# LED_Driver.net
KiCad netlist of a schematic drawn in Altium Designer
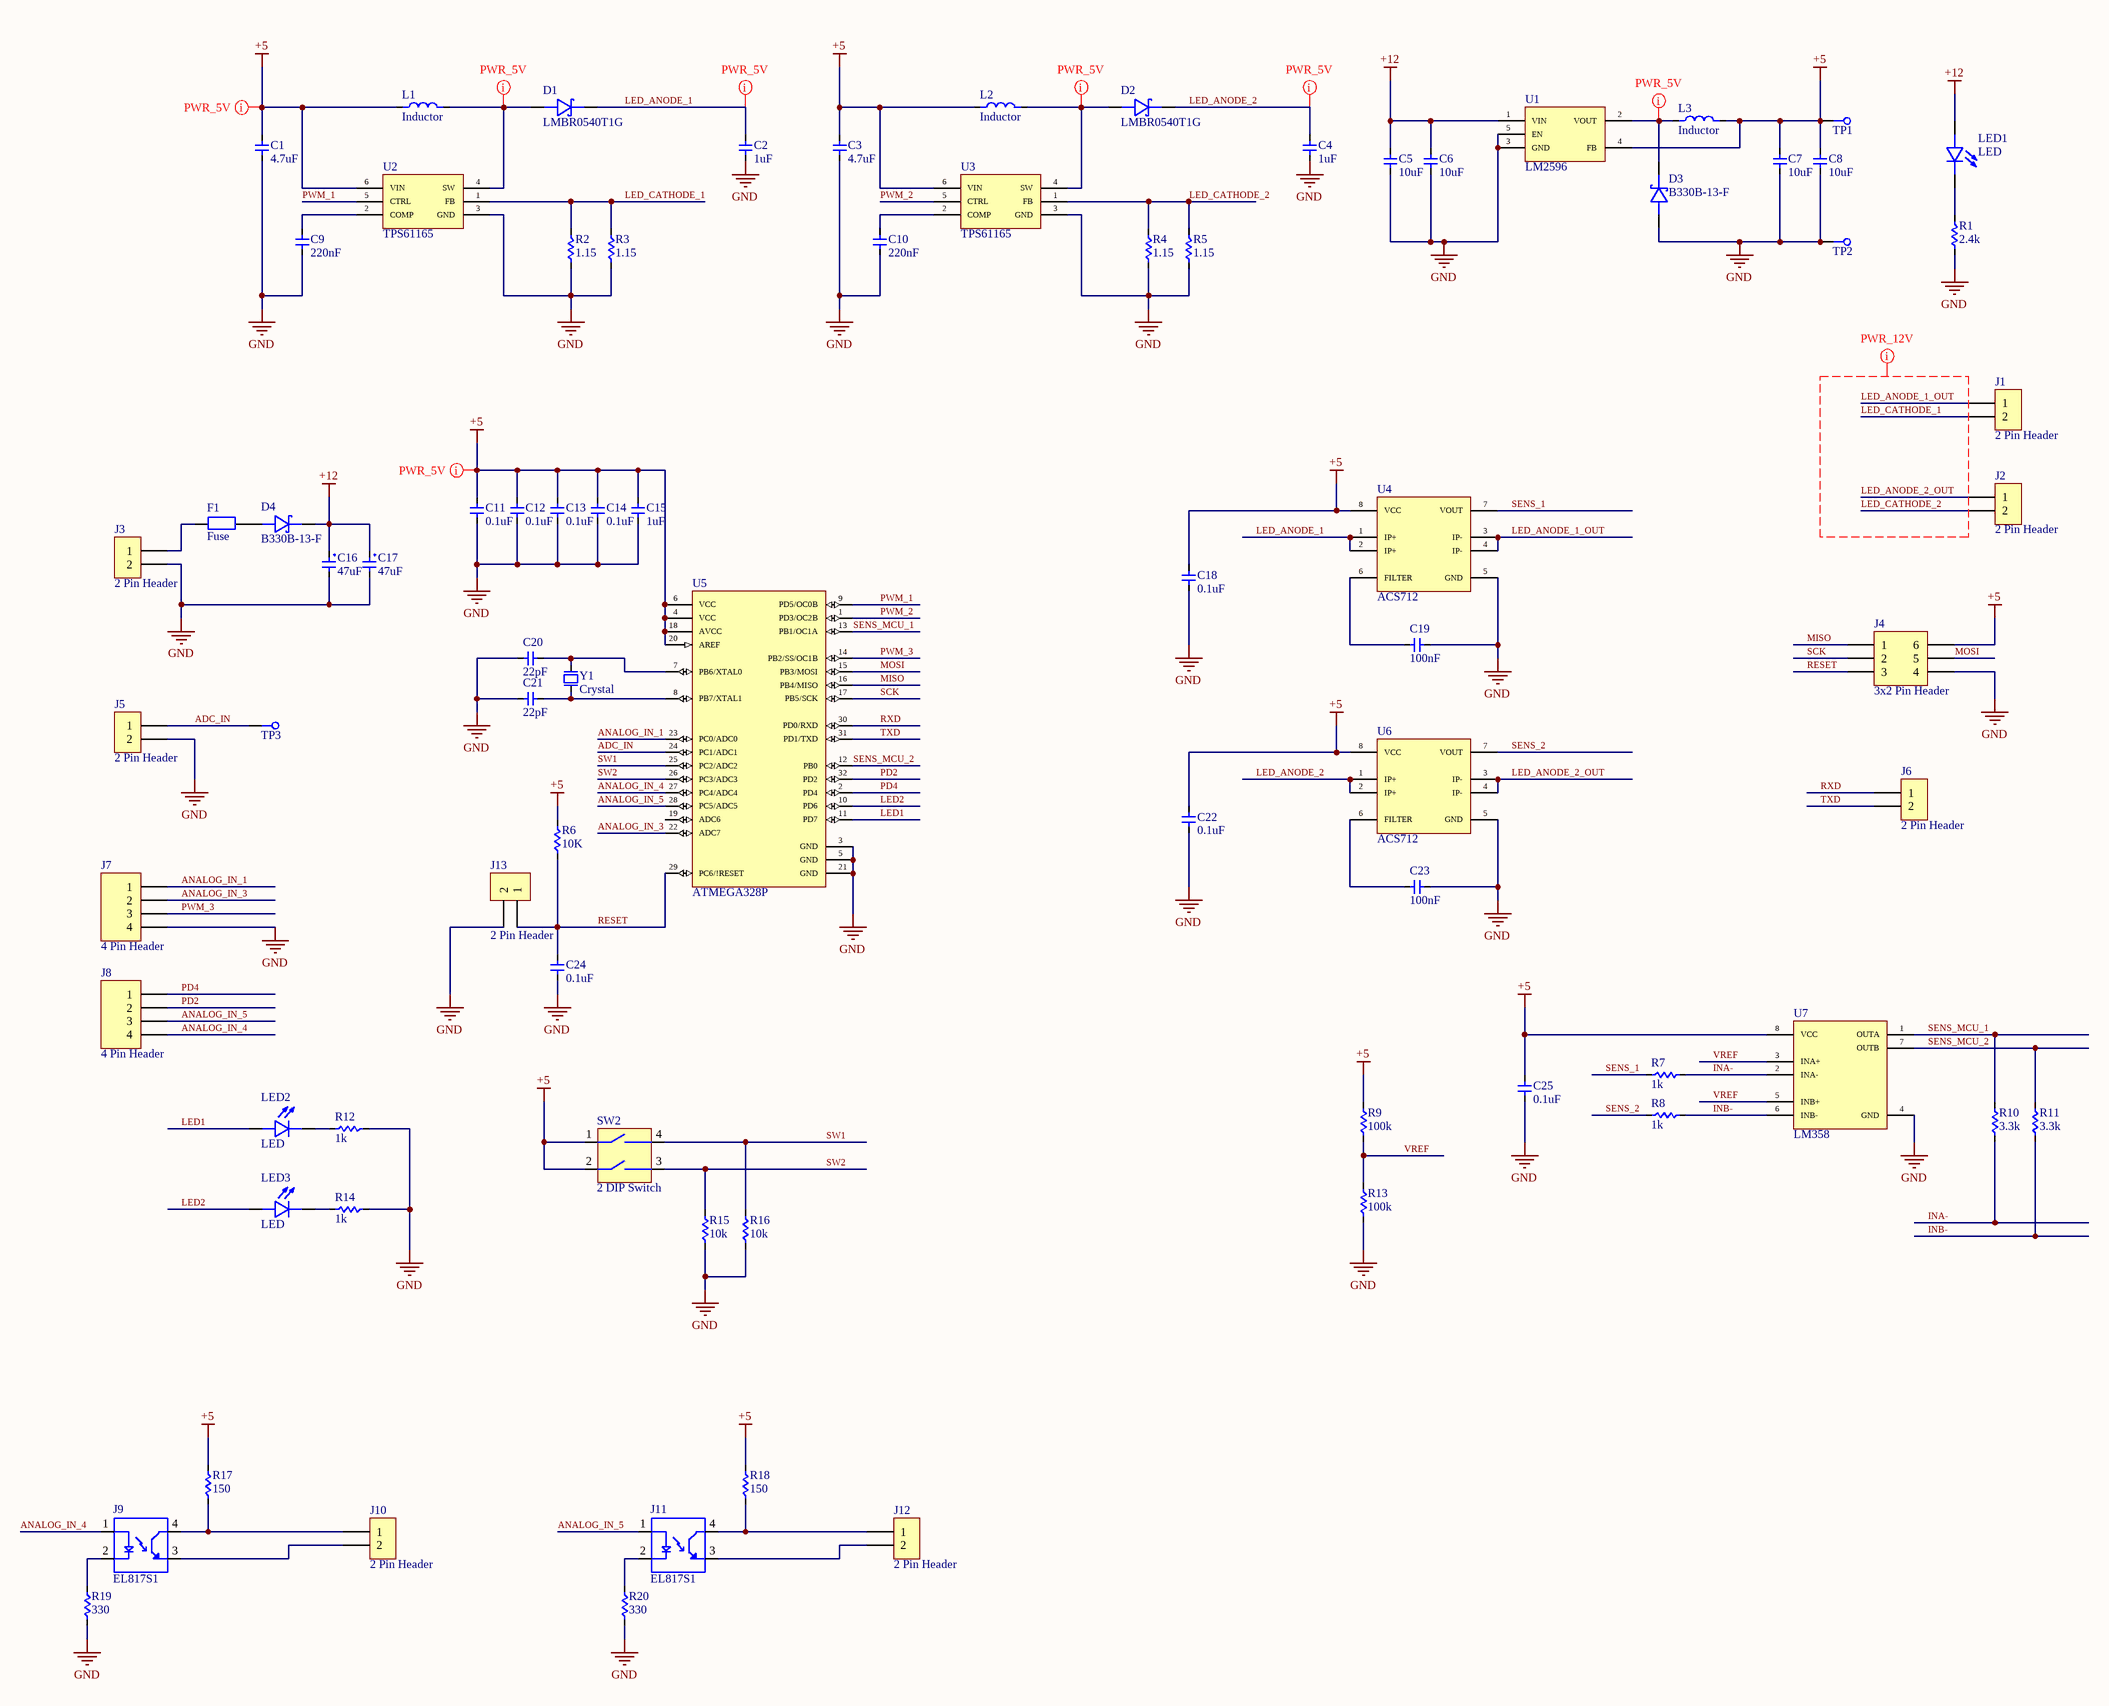
[diagram p0: LED Driver.SchDoc]

(export (version "E")
  (design (tool "Eeschema 10.0.6"))
  (components
    (comp (ref "C1") (value "4.7uF") (footprint "RES603") (libsource (lib "Schlib") (part "Capacitor")))
    (comp (ref "C2") (value "1uF") (footprint "RES603") (libsource (lib "Schlib") (part "Capacitor")))
    (comp (ref "C3") (value "4.7uF") (footprint "RES603") (libsource (lib "Schlib") (part "Capacitor")))
    (comp (ref "C4") (value "1uF") (footprint "RES603") (libsource (lib "Schlib") (part "Capacitor")))
    (comp (ref "C5") (value "10uF") (footprint "RES603") (libsource (lib "Schlib") (part "Capacitor")))
    (comp (ref "C6") (value "10uF") (footprint "RES603") (libsource (lib "Schlib") (part "Capacitor")))
    (comp (ref "C7") (value "10uF") (footprint "RES603") (libsource (lib "Schlib") (part "Capacitor")))
    (comp (ref "C8") (value "10uF") (footprint "RES603") (libsource (lib "Schlib") (part "Capacitor")))
    (comp (ref "C9") (value "220nF") (footprint "RES603") (libsource (lib "Schlib") (part "Capacitor")))
    (comp (ref "C10") (value "220nF") (footprint "RES603") (libsource (lib "Schlib") (part "Capacitor")))
    (comp (ref "C11") (value "0.1uF") (footprint "RES603") (libsource (lib "Schlib") (part "Capacitor")))
    (comp (ref "C12") (value "0.1uF") (footprint "RES603") (libsource (lib "Schlib") (part "Capacitor")))
    (comp (ref "C13") (value "0.1uF") (footprint "RES603") (libsource (lib "Schlib") (part "Capacitor")))
    (comp (ref "C14") (value "0.1uF") (footprint "RES603") (libsource (lib "Schlib") (part "Capacitor")))
    (comp (ref "C15") (value "1uF") (footprint "RES603") (libsource (lib "Schlib") (part "Capacitor")))
    (comp (ref "C16")
      (value "47uF")
      (footprint "VEJ470M1HTR-0607")
      (libsource (lib "Schlib") (part "Cap Pol"))
    )
    (comp (ref "C17")
      (value "47uF")
      (footprint "VEJ470M1HTR-0607")
      (libsource (lib "Schlib") (part "Cap Pol"))
    )
    (comp (ref "C18") (value "0.1uF") (footprint "RES603") (libsource (lib "Schlib") (part "Capacitor")))
    (comp (ref "C19") (value "100nF") (footprint "RES603") (libsource (lib "Schlib") (part "Capacitor")))
    (comp (ref "C20") (value "22pF") (footprint "RES603") (libsource (lib "Schlib") (part "Capacitor")))
    (comp (ref "C21") (value "22pF") (footprint "RES603") (libsource (lib "Schlib") (part "Capacitor")))
    (comp (ref "C22") (value "0.1uF") (footprint "RES603") (libsource (lib "Schlib") (part "Capacitor")))
    (comp (ref "C23") (value "100nF") (footprint "RES603") (libsource (lib "Schlib") (part "Capacitor")))
    (comp (ref "C24") (value "0.1uF") (footprint "RES603") (libsource (lib "Schlib") (part "Capacitor")))
    (comp (ref "C25") (value "0.1uF") (footprint "RES603") (libsource (lib "Schlib") (part "Capacitor")))
    (comp (ref "D1")
      (value "LMBR0540T1G")
      (footprint "LMBR0540T1G")
      (libsource (lib "Schlib") (part "Schottky Diode"))
    )
    (comp (ref "D2")
      (value "LMBR0540T1G")
      (footprint "LMBR0540T1G")
      (libsource (lib "Schlib") (part "Schottky Diode"))
    )
    (comp (ref "D3")
      (value "B330B-13-F")
      (footprint "B330B-13-F")
      (libsource (lib "Schlib") (part "Schottky Diode"))
    )
    (comp (ref "D4")
      (value "B330B-13-F")
      (footprint "B330B-13-F")
      (libsource (lib "Schlib") (part "Schottky Diode"))
    )
    (comp (ref "F1") (value "Fuse") (footprint "39215000000") (libsource (lib "Schlib") (part "Fuse")))
    (comp (ref "J1")
      (value "2 Pin Header")
      (footprint "2POS 2.54mm Pin Header")
      (libsource (lib "Schlib") (part "2 Pin Header"))
    )
    (comp (ref "J2")
      (value "2 Pin Header")
      (footprint "2POS 2.54mm Pin Header")
      (libsource (lib "Schlib") (part "2 Pin Header"))
    )
    (comp (ref "J3")
      (value "2 Pin Header")
      (footprint "2POS 5.08mm Screw Connector")
      (libsource (lib "") (part "2 Pin Header_1"))
    )
    (comp (ref "J4")
      (value "3x2 Pin Header")
      (footprint "2x3POS 2.54mm Pin Header")
      (libsource (lib "Schlib") (part "3x2 Pin Header"))
    )
    (comp (ref "J5")
      (value "2 Pin Header")
      (footprint "2POS 2.54mm Pin Header")
      (libsource (lib "") (part "2 Pin Header_1"))
    )
    (comp (ref "J6")
      (value "2 Pin Header")
      (footprint "2POS 2.54mm Pin Header")
      (libsource (lib "Schlib") (part "2 Pin Header"))
    )
    (comp (ref "J7")
      (value "4 Pin Header")
      (footprint "4POS 2.54mm PIN Header")
      (libsource (lib "Schlib") (part "4 Pin Header"))
    )
    (comp (ref "J8")
      (value "4 Pin Header")
      (footprint "4POS 2.54mm PIN Header")
      (libsource (lib "Schlib") (part "4 Pin Header"))
    )
    (comp (ref "J9") (value "EL817S1") (footprint "EL817S1") (libsource (lib "Schlib") (part "EL817S1")))
    (comp (ref "J10")
      (value "2 Pin Header")
      (footprint "2POS 2.54mm Pin Header")
      (libsource (lib "Schlib") (part "2 Pin Header"))
    )
    (comp (ref "J11") (value "EL817S1") (footprint "EL817S1") (libsource (lib "Schlib") (part "EL817S1")))
    (comp (ref "J12")
      (value "2 Pin Header")
      (footprint "2POS 2.54mm Pin Header")
      (libsource (lib "Schlib") (part "2 Pin Header"))
    )
    (comp (ref "J13")
      (value "2 Pin Header")
      (footprint "2POS 5.08mm Screw Connector")
      (libsource (lib "Schlib") (part "2 Pin Header"))
    )
    (comp (ref "L1")
      (value "Inductor")
      (footprint "CDRH104RNP-220NC")
      (libsource (lib "Schlib") (part "Inductor"))
    )
    (comp (ref "L2")
      (value "Inductor")
      (footprint "CDRH104RNP-220NC")
      (libsource (lib "Schlib") (part "Inductor"))
    )
    (comp (ref "L3")
      (value "Inductor")
      (footprint "CDRH104RNP-220NC")
      (libsource (lib "Schlib") (part "Inductor"))
    )
    (comp (ref "LED1") (value "LED") (footprint "LED603") (libsource (lib "Schlib") (part "LED")))
    (comp (ref "LED2") (value "LED") (footprint "LED603") (libsource (lib "Schlib") (part "LED")))
    (comp (ref "LED3") (value "LED") (footprint "LED603") (libsource (lib "Schlib") (part "LED")))
    (comp (ref "R1") (value "2.4k") (footprint "RES805") (libsource (lib "Schlib") (part "Resistor")))
    (comp (ref "R2") (value "1.15") (footprint "RES805") (libsource (lib "Schlib") (part "Resistor")))
    (comp (ref "R3") (value "1.15") (footprint "RES805") (libsource (lib "Schlib") (part "Resistor")))
    (comp (ref "R4") (value "1.15") (footprint "RES805") (libsource (lib "Schlib") (part "Resistor")))
    (comp (ref "R5") (value "1.15") (footprint "RES805") (libsource (lib "Schlib") (part "Resistor")))
    (comp (ref "R6") (value "10K") (footprint "RES603") (libsource (lib "Schlib") (part "Resistor")))
    (comp (ref "R7") (value "1k") (footprint "RES603") (libsource (lib "Schlib") (part "Resistor")))
    (comp (ref "R8") (value "1k") (footprint "RES603") (libsource (lib "Schlib") (part "Resistor")))
    (comp (ref "R9") (value "100k") (footprint "RES603") (libsource (lib "Schlib") (part "Resistor")))
    (comp (ref "R10") (value "3.3k") (footprint "RES603") (libsource (lib "Schlib") (part "Resistor")))
    (comp (ref "R11") (value "3.3k") (footprint "RES603") (libsource (lib "Schlib") (part "Resistor")))
    (comp (ref "R12") (value "1k") (footprint "RES805") (libsource (lib "Schlib") (part "Resistor")))
    (comp (ref "R13") (value "100k") (footprint "RES603") (libsource (lib "Schlib") (part "Resistor")))
    (comp (ref "R14") (value "1k") (footprint "RES805") (libsource (lib "Schlib") (part "Resistor")))
    (comp (ref "R15") (value "10k") (footprint "RES603") (libsource (lib "Schlib") (part "Resistor")))
    (comp (ref "R16") (value "10k") (footprint "RES603") (libsource (lib "Schlib") (part "Resistor")))
    (comp (ref "R17") (value "150") (footprint "RES805") (libsource (lib "Schlib") (part "Resistor")))
    (comp (ref "R18") (value "150") (footprint "RES805") (libsource (lib "Schlib") (part "Resistor")))
    (comp (ref "R19") (value "330") (footprint "RES805") (libsource (lib "Schlib") (part "Resistor")))
    (comp (ref "R20") (value "330") (footprint "RES805") (libsource (lib "Schlib") (part "Resistor")))
    (comp (ref "SW2")
      (value "2 DIP Switch")
      (footprint "EM-02KP")
      (libsource (lib "Schlib") (part "2 DIP Switch"))
    )
    (comp (ref "TP1")
      (value "Test Point")
      (footprint "TP SMD")
      (libsource (lib "Schlib") (part "Test Point"))
    )
    (comp (ref "TP2")
      (value "Test Point")
      (footprint "TP SMD")
      (libsource (lib "Schlib") (part "Test Point"))
    )
    (comp (ref "TP3")
      (value "Test Point")
      (footprint "TP SMD")
      (libsource (lib "Schlib") (part "Test Point"))
    )
    (comp (ref "U1") (value "LM2596") (footprint "LM2596-TO263") (libsource (lib "Schlib") (part "LM2596")))
    (comp (ref "U2") (value "TPS61165") (footprint "TPS611DRVR") (libsource (lib "Schlib") (part "TPS61165")))
    (comp (ref "U3") (value "TPS61165") (footprint "TPS611DRVR") (libsource (lib "Schlib") (part "TPS61165")))
    (comp (ref "U4")
      (value "ACS712")
      (footprint "SOIC127P600X175-8N")
      (libsource (lib "Schlib") (part "ACS712"))
    )
    (comp (ref "U5")
      (value "ATMEGA328P")
      (footprint "ATMEGA328P-AU")
      (libsource (lib "Schlib") (part "ATMEGA328P"))
    )
    (comp (ref "U6")
      (value "ACS712")
      (footprint "SOIC127P600X175-8N")
      (libsource (lib "Schlib") (part "ACS712"))
    )
    (comp (ref "U7")
      (value "LM358")
      (footprint "SOIC127P600X175-8N")
      (libsource (lib "Schlib") (part "LM358"))
    )
    (comp (ref "Y1")
      (value "Crystal")
      (footprint "X503216MSB2GI")
      (libsource (lib "Schlib") (part "Crystal"))
    )
  )
  (nets
    (net (code "1") (name "+5") (class "Default")
      (node (ref "C1") (pin "2") (pinfunction "2_2") (pintype "passive"))
      (node (ref "C11") (pin "2") (pinfunction "2_2") (pintype "passive"))
      (node (ref "C12") (pin "2") (pinfunction "2_2") (pintype "passive"))
      (node (ref "C13") (pin "2") (pinfunction "2_2") (pintype "passive"))
      (node (ref "C14") (pin "2") (pinfunction "2_2") (pintype "passive"))
      (node (ref "C15") (pin "2") (pinfunction "2_2") (pintype "passive"))
      (node (ref "C18") (pin "2") (pinfunction "2_2") (pintype "passive"))
      (node (ref "C22") (pin "2") (pinfunction "2_2") (pintype "passive"))
      (node (ref "C25") (pin "2") (pinfunction "2_2") (pintype "passive"))
      (node (ref "C3") (pin "2") (pinfunction "2_2") (pintype "passive"))
      (node (ref "C7") (pin "2") (pinfunction "2_2") (pintype "passive"))
      (node (ref "C8") (pin "2") (pinfunction "2_2") (pintype "passive"))
      (node (ref "J4") (pin "6") (pinfunction "6_6") (pintype "passive"))
      (node (ref "L1") (pin "1") (pinfunction "1_1") (pintype "passive"))
      (node (ref "L2") (pin "1") (pinfunction "1_1") (pintype "passive"))
      (node (ref "L3") (pin "2") (pinfunction "2_2") (pintype "passive"))
      (node (ref "R17") (pin "2") (pinfunction "2_2") (pintype "passive"))
      (node (ref "R18") (pin "2") (pinfunction "2_2") (pintype "passive"))
      (node (ref "R6") (pin "2") (pinfunction "2_2") (pintype "passive"))
      (node (ref "R9") (pin "2") (pinfunction "2_2") (pintype "passive"))
      (node (ref "SW2") (pin "1") (pinfunction "1_1") (pintype "passive"))
      (node (ref "SW2") (pin "2") (pinfunction "2_2") (pintype "passive"))
      (node (ref "TP1") (pin "1") (pinfunction "1_1") (pintype "passive"))
      (node (ref "U1") (pin "4") (pinfunction "FB_4") (pintype "passive"))
      (node (ref "U2") (pin "6") (pinfunction "VIN_6") (pintype "passive"))
      (node (ref "U3") (pin "6") (pinfunction "VIN_6") (pintype "passive"))
      (node (ref "U4") (pin "8") (pinfunction "VCC_8") (pintype "passive"))
      (node (ref "U5") (pin "18") (pinfunction "AVCC_18") (pintype "power_in"))
      (node (ref "U5") (pin "20") (pinfunction "AREF_20") (pintype "input"))
      (node (ref "U5") (pin "4") (pinfunction "VCC_4") (pintype "power_in"))
      (node (ref "U5") (pin "6") (pinfunction "VCC_6") (pintype "power_in"))
      (node (ref "U6") (pin "8") (pinfunction "VCC_8") (pintype "passive"))
      (node (ref "U7") (pin "8") (pinfunction "VCC_8") (pintype "passive"))
    )
    (net (code "2") (name "+12") (class "Default")
      (node (ref "C16") (pin "1") (pinfunction "1_1") (pintype "passive"))
      (node (ref "C17") (pin "1") (pinfunction "1_1") (pintype "passive"))
      (node (ref "C5") (pin "2") (pinfunction "2_2") (pintype "passive"))
      (node (ref "C6") (pin "2") (pinfunction "2_2") (pintype "passive"))
      (node (ref "D4") (pin "C") (pinfunction "C_C") (pintype "passive"))
      (node (ref "LED1") (pin "A") (pinfunction "A_A") (pintype "passive"))
      (node (ref "U1") (pin "1") (pinfunction "VIN_1") (pintype "passive"))
    )
    (net (code "3") (name "/ADC_IN") (class "Default")
      (node (ref "J5") (pin "1") (pinfunction "1_1") (pintype "passive"))
      (node (ref "TP3") (pin "1") (pinfunction "1_1") (pintype "passive"))
      (node (ref "U5") (pin "24") (pinfunction "PC1/ADC1_24") (pintype "bidirectional"))
    )
    (net (code "4") (name "/ANALOG_IN_1") (class "Default")
      (node (ref "J7") (pin "1") (pinfunction "1_1") (pintype "passive"))
      (node (ref "U5") (pin "23") (pinfunction "PC0/ADC0_23") (pintype "bidirectional"))
    )
    (net (code "5") (name "/ANALOG_IN_3") (class "Default")
      (node (ref "J7") (pin "2") (pinfunction "2_2") (pintype "passive"))
      (node (ref "U5") (pin "22") (pinfunction "ADC7_22") (pintype "bidirectional"))
    )
    (net (code "6") (name "/ANALOG_IN_4") (class "Default")
      (node (ref "J8") (pin "4") (pinfunction "4_4") (pintype "passive"))
      (node (ref "J9") (pin "1") (pinfunction "A_1") (pintype "passive"))
      (node (ref "U5") (pin "27") (pinfunction "PC4/ADC4_27") (pintype "bidirectional"))
    )
    (net (code "7") (name "/ANALOG_IN_5") (class "Default")
      (node (ref "J11") (pin "1") (pinfunction "A_1") (pintype "passive"))
      (node (ref "J8") (pin "3") (pinfunction "3_3") (pintype "passive"))
      (node (ref "U5") (pin "28") (pinfunction "PC5/ADC5_28") (pintype "bidirectional"))
    )
    (net (code "8") (name "/INA-") (class "Default")
      (node (ref "R10") (pin "2") (pinfunction "2_2") (pintype "passive"))
      (node (ref "R7") (pin "1") (pinfunction "1_1") (pintype "passive"))
      (node (ref "U7") (pin "2") (pinfunction "INA-_2") (pintype "passive"))
    )
    (net (code "9") (name "/INB-") (class "Default")
      (node (ref "R11") (pin "2") (pinfunction "2_2") (pintype "passive"))
      (node (ref "R8") (pin "1") (pinfunction "1_1") (pintype "passive"))
      (node (ref "U7") (pin "6") (pinfunction "INB-_6") (pintype "passive"))
    )
    (net (code "10") (name "/LED1") (class "Default")
      (node (ref "LED2") (pin "A") (pinfunction "A_A") (pintype "passive"))
      (node (ref "U5") (pin "11") (pinfunction "PD7_11") (pintype "bidirectional"))
    )
    (net (code "11") (name "/LED2") (class "Default")
      (node (ref "LED3") (pin "A") (pinfunction "A_A") (pintype "passive"))
      (node (ref "U5") (pin "10") (pinfunction "PD6_10") (pintype "bidirectional"))
    )
    (net (code "12") (name "/LED_ANODE_1") (class "Default")
      (node (ref "C2") (pin "2") (pinfunction "2_2") (pintype "passive"))
      (node (ref "D1") (pin "C") (pinfunction "C_C") (pintype "passive"))
      (node (ref "U4") (pin "1") (pinfunction "IP+_1") (pintype "passive"))
      (node (ref "U4") (pin "2") (pinfunction "IP+_2") (pintype "passive"))
    )
    (net (code "13") (name "/LED_ANODE_1_OUT") (class "Default")
      (node (ref "J1") (pin "1") (pinfunction "1_1") (pintype "passive"))
      (node (ref "U4") (pin "3") (pinfunction "IP-_3") (pintype "passive"))
      (node (ref "U4") (pin "4") (pinfunction "IP-_4") (pintype "passive"))
    )
    (net (code "14") (name "/LED_ANODE_2") (class "Default")
      (node (ref "C4") (pin "2") (pinfunction "2_2") (pintype "passive"))
      (node (ref "D2") (pin "C") (pinfunction "C_C") (pintype "passive"))
      (node (ref "U6") (pin "1") (pinfunction "IP+_1") (pintype "passive"))
      (node (ref "U6") (pin "2") (pinfunction "IP+_2") (pintype "passive"))
    )
    (net (code "15") (name "/LED_ANODE_2_OUT") (class "Default")
      (node (ref "J2") (pin "1") (pinfunction "1_1") (pintype "passive"))
      (node (ref "U6") (pin "3") (pinfunction "IP-_3") (pintype "passive"))
      (node (ref "U6") (pin "4") (pinfunction "IP-_4") (pintype "passive"))
    )
    (net (code "16") (name "/LED_CATHODE_1") (class "Default")
      (node (ref "J1") (pin "2") (pinfunction "2_2") (pintype "passive"))
      (node (ref "R2") (pin "2") (pinfunction "2_2") (pintype "passive"))
      (node (ref "R3") (pin "2") (pinfunction "2_2") (pintype "passive"))
      (node (ref "U2") (pin "1") (pinfunction "FB_1") (pintype "passive"))
    )
    (net (code "17") (name "/LED_CATHODE_2") (class "Default")
      (node (ref "J2") (pin "2") (pinfunction "2_2") (pintype "passive"))
      (node (ref "R4") (pin "2") (pinfunction "2_2") (pintype "passive"))
      (node (ref "R5") (pin "2") (pinfunction "2_2") (pintype "passive"))
      (node (ref "U3") (pin "1") (pinfunction "FB_1") (pintype "passive"))
    )
    (net (code "18") (name "/MISO") (class "Default")
      (node (ref "J4") (pin "1") (pinfunction "1_1") (pintype "passive"))
      (node (ref "U5") (pin "16") (pinfunction "PB4/MISO_16") (pintype "bidirectional"))
    )
    (net (code "19") (name "/MOSI") (class "Default")
      (node (ref "J4") (pin "5") (pinfunction "5_5") (pintype "passive"))
      (node (ref "U5") (pin "15") (pinfunction "PB3/MOSI_15") (pintype "bidirectional"))
    )
    (net (code "20") (name "/PD2") (class "Default")
      (node (ref "J8") (pin "2") (pinfunction "2_2") (pintype "passive"))
      (node (ref "U5") (pin "32") (pinfunction "PD2_32") (pintype "bidirectional"))
    )
    (net (code "21") (name "/PD4") (class "Default")
      (node (ref "J8") (pin "1") (pinfunction "1_1") (pintype "passive"))
      (node (ref "U5") (pin "2") (pinfunction "PD4_2") (pintype "bidirectional"))
    )
    (net (code "22") (name "/PWM_1") (class "Default")
      (node (ref "U2") (pin "5") (pinfunction "CTRL_5") (pintype "passive"))
      (node (ref "U5") (pin "9") (pinfunction "PD5/OC0B_9") (pintype "bidirectional"))
    )
    (net (code "23") (name "/PWM_2") (class "Default")
      (node (ref "U3") (pin "5") (pinfunction "CTRL_5") (pintype "passive"))
      (node (ref "U5") (pin "1") (pinfunction "PD3/OC2B_1") (pintype "bidirectional"))
    )
    (net (code "24") (name "/PWM_3") (class "Default")
      (node (ref "J7") (pin "3") (pinfunction "3_3") (pintype "passive"))
      (node (ref "U5") (pin "14") (pinfunction "PB2/SS/OC1B_14") (pintype "bidirectional"))
    )
    (net (code "25") (name "/RESET") (class "Default")
      (node (ref "C24") (pin "2") (pinfunction "2_2") (pintype "passive"))
      (node (ref "J13") (pin "1") (pinfunction "1_1") (pintype "passive"))
      (node (ref "J4") (pin "3") (pinfunction "3_3") (pintype "passive"))
      (node (ref "R6") (pin "1") (pinfunction "1_1") (pintype "passive"))
      (node (ref "U5") (pin "29") (pinfunction "PC6/!RESET_29") (pintype "bidirectional"))
    )
    (net (code "26") (name "/RXD") (class "Default")
      (node (ref "J6") (pin "1") (pinfunction "1_1") (pintype "passive"))
      (node (ref "U5") (pin "30") (pinfunction "PD0/RXD_30") (pintype "bidirectional"))
    )
    (net (code "27") (name "/SCK") (class "Default")
      (node (ref "J4") (pin "2") (pinfunction "2_2") (pintype "passive"))
      (node (ref "U5") (pin "17") (pinfunction "PB5/SCK_17") (pintype "bidirectional"))
    )
    (net (code "28") (name "/SENS_1") (class "Default")
      (node (ref "R7") (pin "2") (pinfunction "2_2") (pintype "passive"))
      (node (ref "U4") (pin "7") (pinfunction "VOUT_7") (pintype "passive"))
    )
    (net (code "29") (name "/SENS_2") (class "Default")
      (node (ref "R8") (pin "2") (pinfunction "2_2") (pintype "passive"))
      (node (ref "U6") (pin "7") (pinfunction "VOUT_7") (pintype "passive"))
    )
    (net (code "30") (name "/SENS_MCU_1") (class "Default")
      (node (ref "R10") (pin "1") (pinfunction "1_1") (pintype "passive"))
      (node (ref "U5") (pin "13") (pinfunction "PB1/OC1A_13") (pintype "bidirectional"))
      (node (ref "U7") (pin "1") (pinfunction "OUTA_1") (pintype "passive"))
    )
    (net (code "31") (name "/SENS_MCU_2") (class "Default")
      (node (ref "R11") (pin "1") (pinfunction "1_1") (pintype "passive"))
      (node (ref "U5") (pin "12") (pinfunction "PB0_12") (pintype "bidirectional"))
      (node (ref "U7") (pin "7") (pinfunction "OUTB_7") (pintype "passive"))
    )
    (net (code "32") (name "/SW1") (class "Default")
      (node (ref "R16") (pin "2") (pinfunction "2_2") (pintype "passive"))
      (node (ref "SW2") (pin "4") (pinfunction "4_4") (pintype "passive"))
      (node (ref "U5") (pin "25") (pinfunction "PC2/ADC2_25") (pintype "bidirectional"))
    )
    (net (code "33") (name "/SW2") (class "Default")
      (node (ref "R15") (pin "2") (pinfunction "2_2") (pintype "passive"))
      (node (ref "SW2") (pin "3") (pinfunction "3_3") (pintype "passive"))
      (node (ref "U5") (pin "26") (pinfunction "PC3/ADC3_26") (pintype "bidirectional"))
    )
    (net (code "34") (name "/TXD") (class "Default")
      (node (ref "J6") (pin "2") (pinfunction "2_2") (pintype "passive"))
      (node (ref "U5") (pin "31") (pinfunction "PD1/TXD_31") (pintype "bidirectional"))
    )
    (net (code "35") (name "/VREF") (class "Default")
      (node (ref "R13") (pin "2") (pinfunction "2_2") (pintype "passive"))
      (node (ref "R9") (pin "1") (pinfunction "1_1") (pintype "passive"))
      (node (ref "U7") (pin "3") (pinfunction "INA+_3") (pintype "passive"))
      (node (ref "U7") (pin "5") (pinfunction "INB+_5") (pintype "passive"))
    )
    (net (code "36") (name "GND") (class "Default")
      (node (ref "C1") (pin "1") (pinfunction "1_1") (pintype "passive"))
      (node (ref "C10") (pin "1") (pinfunction "1_1") (pintype "passive"))
      (node (ref "C11") (pin "1") (pinfunction "1_1") (pintype "passive"))
      (node (ref "C12") (pin "1") (pinfunction "1_1") (pintype "passive"))
      (node (ref "C13") (pin "1") (pinfunction "1_1") (pintype "passive"))
      (node (ref "C14") (pin "1") (pinfunction "1_1") (pintype "passive"))
      (node (ref "C15") (pin "1") (pinfunction "1_1") (pintype "passive"))
      (node (ref "C16") (pin "2") (pinfunction "2_2") (pintype "passive"))
      (node (ref "C17") (pin "2") (pinfunction "2_2") (pintype "passive"))
      (node (ref "C18") (pin "1") (pinfunction "1_1") (pintype "passive"))
      (node (ref "C19") (pin "1") (pinfunction "1_1") (pintype "passive"))
      (node (ref "C2") (pin "1") (pinfunction "1_1") (pintype "passive"))
      (node (ref "C20") (pin "2") (pinfunction "2_2") (pintype "passive"))
      (node (ref "C21") (pin "2") (pinfunction "2_2") (pintype "passive"))
      (node (ref "C22") (pin "1") (pinfunction "1_1") (pintype "passive"))
      (node (ref "C23") (pin "1") (pinfunction "1_1") (pintype "passive"))
      (node (ref "C24") (pin "1") (pinfunction "1_1") (pintype "passive"))
      (node (ref "C25") (pin "1") (pinfunction "1_1") (pintype "passive"))
      (node (ref "C3") (pin "1") (pinfunction "1_1") (pintype "passive"))
      (node (ref "C4") (pin "1") (pinfunction "1_1") (pintype "passive"))
      (node (ref "C5") (pin "1") (pinfunction "1_1") (pintype "passive"))
      (node (ref "C6") (pin "1") (pinfunction "1_1") (pintype "passive"))
      (node (ref "C7") (pin "1") (pinfunction "1_1") (pintype "passive"))
      (node (ref "C8") (pin "1") (pinfunction "1_1") (pintype "passive"))
      (node (ref "C9") (pin "1") (pinfunction "1_1") (pintype "passive"))
      (node (ref "D3") (pin "A") (pinfunction "A_A") (pintype "passive"))
      (node (ref "J13") (pin "2") (pinfunction "2_2") (pintype "passive"))
      (node (ref "J3") (pin "2") (pinfunction "2_2") (pintype "passive"))
      (node (ref "J4") (pin "4") (pinfunction "4_4") (pintype "passive"))
      (node (ref "J5") (pin "2") (pinfunction "2_2") (pintype "passive"))
      (node (ref "J7") (pin "4") (pinfunction "4_4") (pintype "passive"))
      (node (ref "R1") (pin "1") (pinfunction "1_1") (pintype "passive"))
      (node (ref "R12") (pin "2") (pinfunction "2_2") (pintype "passive"))
      (node (ref "R13") (pin "1") (pinfunction "1_1") (pintype "passive"))
      (node (ref "R14") (pin "2") (pinfunction "2_2") (pintype "passive"))
      (node (ref "R15") (pin "1") (pinfunction "1_1") (pintype "passive"))
      (node (ref "R16") (pin "1") (pinfunction "1_1") (pintype "passive"))
      (node (ref "R19") (pin "1") (pinfunction "1_1") (pintype "passive"))
      (node (ref "R2") (pin "1") (pinfunction "1_1") (pintype "passive"))
      (node (ref "R20") (pin "1") (pinfunction "1_1") (pintype "passive"))
      (node (ref "R3") (pin "1") (pinfunction "1_1") (pintype "passive"))
      (node (ref "R4") (pin "1") (pinfunction "1_1") (pintype "passive"))
      (node (ref "R5") (pin "1") (pinfunction "1_1") (pintype "passive"))
      (node (ref "TP2") (pin "1") (pinfunction "1_1") (pintype "passive"))
      (node (ref "U1") (pin "3") (pinfunction "GND_3") (pintype "passive"))
      (node (ref "U1") (pin "5") (pinfunction "EN_5") (pintype "passive"))
      (node (ref "U2") (pin "3") (pinfunction "GND_3") (pintype "passive"))
      (node (ref "U3") (pin "3") (pinfunction "GND_3") (pintype "passive"))
      (node (ref "U4") (pin "5") (pinfunction "GND_5") (pintype "passive"))
      (node (ref "U5") (pin "21") (pinfunction "GND_21") (pintype "power_in"))
      (node (ref "U5") (pin "3") (pinfunction "GND_3") (pintype "power_in"))
      (node (ref "U5") (pin "5") (pinfunction "GND_5") (pintype "power_in"))
      (node (ref "U6") (pin "5") (pinfunction "GND_5") (pintype "passive"))
      (node (ref "U7") (pin "4") (pinfunction "GND_4") (pintype "passive"))
    )
    (net (code "37") (name "Net-(D4-PadA)") (class "Default")
      (node (ref "D4") (pin "A") (pinfunction "A_A") (pintype "passive"))
      (node (ref "F1") (pin "2") (pinfunction "2_2") (pintype "passive"))
    )
    (net (code "38") (name "Net-(F1-Pad1)") (class "Default")
      (node (ref "F1") (pin "1") (pinfunction "1_1") (pintype "passive"))
      (node (ref "J3") (pin "1") (pinfunction "1_1") (pintype "passive"))
    )
    (net (code "39") (name "Net-(J9-C)") (class "Default")
      (node (ref "J9") (pin "2") (pinfunction "C_2") (pintype "passive"))
      (node (ref "R19") (pin "2") (pinfunction "2_2") (pintype "passive"))
    )
    (net (code "40") (name "Net-(J9-CT)") (class "Default")
      (node (ref "J10") (pin "1") (pinfunction "1_1") (pintype "passive"))
      (node (ref "J9") (pin "4") (pinfunction "CT_4") (pintype "passive"))
      (node (ref "R17") (pin "1") (pinfunction "1_1") (pintype "passive"))
    )
    (net (code "41") (name "Net-(J9-ET)") (class "Default")
      (node (ref "J10") (pin "2") (pinfunction "2_2") (pintype "passive"))
      (node (ref "J9") (pin "3") (pinfunction "ET_3") (pintype "passive"))
    )
    (net (code "42") (name "Net-(J11-C)") (class "Default")
      (node (ref "J11") (pin "2") (pinfunction "C_2") (pintype "passive"))
      (node (ref "R20") (pin "2") (pinfunction "2_2") (pintype "passive"))
    )
    (net (code "43") (name "Net-(J11-CT)") (class "Default")
      (node (ref "J11") (pin "4") (pinfunction "CT_4") (pintype "passive"))
      (node (ref "J12") (pin "1") (pinfunction "1_1") (pintype "passive"))
      (node (ref "R18") (pin "1") (pinfunction "1_1") (pintype "passive"))
    )
    (net (code "44") (name "Net-(J11-ET)") (class "Default")
      (node (ref "J11") (pin "3") (pinfunction "ET_3") (pintype "passive"))
      (node (ref "J12") (pin "2") (pinfunction "2_2") (pintype "passive"))
    )
    (net (code "45") (name "Net-(LED1-PadC)") (class "Default")
      (node (ref "LED1") (pin "C") (pinfunction "C_C") (pintype "passive"))
      (node (ref "R1") (pin "2") (pinfunction "2_2") (pintype "passive"))
    )
    (net (code "46") (name "Net-(LED2-PadC)") (class "Default")
      (node (ref "LED2") (pin "C") (pinfunction "C_C") (pintype "passive"))
      (node (ref "R12") (pin "1") (pinfunction "1_1") (pintype "passive"))
    )
    (net (code "47") (name "Net-(LED3-PadC)") (class "Default")
      (node (ref "LED3") (pin "C") (pinfunction "C_C") (pintype "passive"))
      (node (ref "R14") (pin "1") (pinfunction "1_1") (pintype "passive"))
    )
    (net (code "48") (name "Net-(U1-VOUT)") (class "Default")
      (node (ref "D3") (pin "C") (pinfunction "C_C") (pintype "passive"))
      (node (ref "L3") (pin "1") (pinfunction "1_1") (pintype "passive"))
      (node (ref "U1") (pin "2") (pinfunction "VOUT_2") (pintype "passive"))
    )
    (net (code "49") (name "Net-(U2-COMP)") (class "Default")
      (node (ref "C9") (pin "2") (pinfunction "2_2") (pintype "passive"))
      (node (ref "U2") (pin "2") (pinfunction "COMP_2") (pintype "passive"))
    )
    (net (code "50") (name "Net-(U2-SW)") (class "Default")
      (node (ref "D1") (pin "A") (pinfunction "A_A") (pintype "passive"))
      (node (ref "L1") (pin "2") (pinfunction "2_2") (pintype "passive"))
      (node (ref "U2") (pin "4") (pinfunction "SW_4") (pintype "passive"))
    )
    (net (code "51") (name "Net-(U3-COMP)") (class "Default")
      (node (ref "C10") (pin "2") (pinfunction "2_2") (pintype "passive"))
      (node (ref "U3") (pin "2") (pinfunction "COMP_2") (pintype "passive"))
    )
    (net (code "52") (name "Net-(U3-SW)") (class "Default")
      (node (ref "D2") (pin "A") (pinfunction "A_A") (pintype "passive"))
      (node (ref "L2") (pin "2") (pinfunction "2_2") (pintype "passive"))
      (node (ref "U3") (pin "4") (pinfunction "SW_4") (pintype "passive"))
    )
    (net (code "53") (name "Net-(U4-FILTER)") (class "Default")
      (node (ref "C19") (pin "2") (pinfunction "2_2") (pintype "passive"))
      (node (ref "U4") (pin "6") (pinfunction "FILTER_6") (pintype "passive"))
    )
    (net (code "54") (name "Net-(U5-PB6{slash}XTAL0)") (class "Default")
      (node (ref "C20") (pin "1") (pinfunction "1_1") (pintype "passive"))
      (node (ref "U5") (pin "7") (pinfunction "PB6/XTAL0_7") (pintype "bidirectional"))
      (node (ref "Y1") (pin "2") (pinfunction "2_2") (pintype "passive"))
    )
    (net (code "55") (name "Net-(U5-PB7{slash}XTAL1)") (class "Default")
      (node (ref "C21") (pin "1") (pinfunction "1_1") (pintype "passive"))
      (node (ref "U5") (pin "8") (pinfunction "PB7/XTAL1_8") (pintype "bidirectional"))
      (node (ref "Y1") (pin "1") (pinfunction "1_1") (pintype "passive"))
    )
    (net (code "56") (name "Net-(U6-FILTER)") (class "Default")
      (node (ref "C23") (pin "2") (pinfunction "2_2") (pintype "passive"))
      (node (ref "U6") (pin "6") (pinfunction "FILTER_6") (pintype "passive"))
    )
    (net (code "57") (name "unconnected-(U5-ADC6-Pad19)") (class "Default")
      (node (ref "U5") (pin "19") (pinfunction "ADC6_19") (pintype "bidirectional"))
    )
  )
)
